# SCH_esp32-custom_2024-02-02.net
KiCad netlist of a schematic drawn in EasyEDA
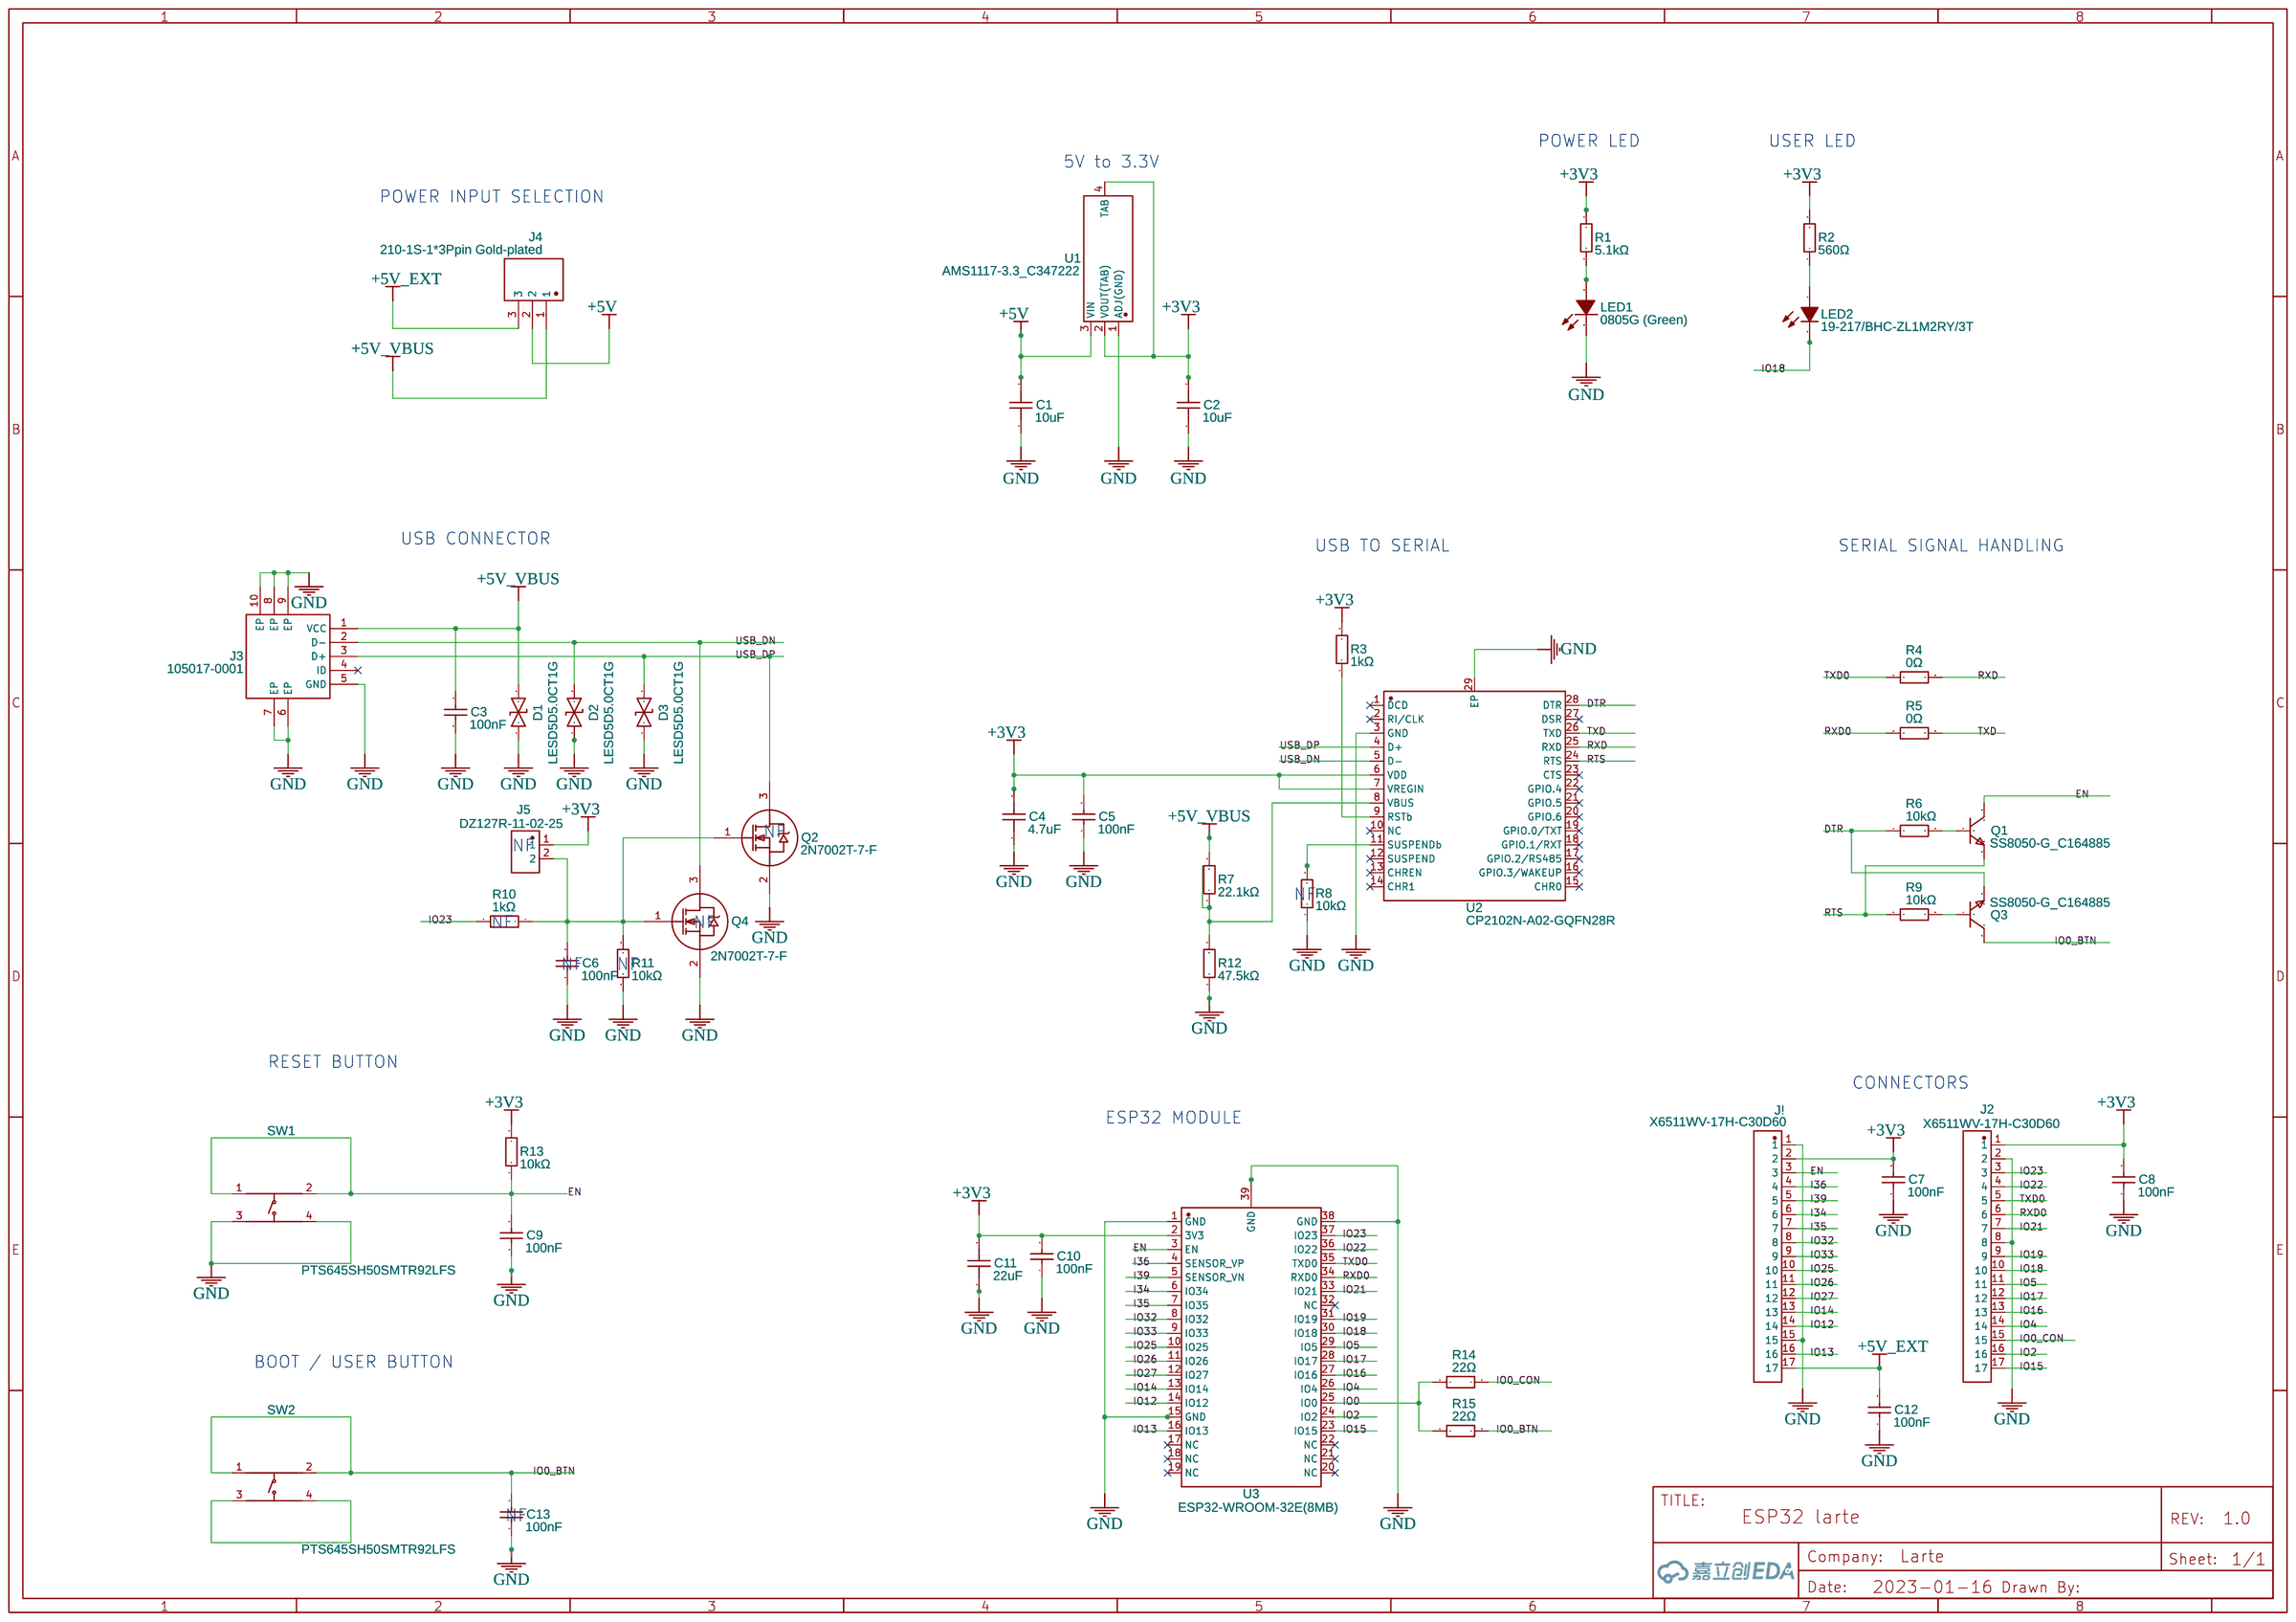
[diagram p0: schematic sheet]

(export (version "E")
  (design (tool "Eeschema 10.0.6"))
  (components
    (comp (ref "C1")
      (value "10uF")
      (fields
        (field (name "Manufacturer Part") "CL05A106MP5NUNC")
        (field (name "Manufacturer") "SAMSUNG(三星)")
      )
      (libsource (lib "") (part "CL05A106MP5NUNC_C315248"))
    )
    (comp (ref "C2")
      (value "10uF")
      (fields
        (field (name "Manufacturer Part") "CL05A106MP5NUNC")
        (field (name "Manufacturer") "SAMSUNG(三星)")
      )
      (libsource (lib "") (part "CL05A106MP5NUNC_C315248"))
    )
    (comp (ref "C3")
      (value "100nF")
      (fields
        (field (name "Manufacturer Part") "CL05B104KO5NNNC")
        (field (name "Manufacturer") "SAMSUNG(三星)")
      )
      (libsource (lib "") (part "CL05B104KO5NNNC"))
    )
    (comp (ref "C4")
      (value "4.7uF")
      (fields
        (field (name "Manufacturer Part") "CL05A475KP5NRNC")
        (field (name "Manufacturer") "SAMSUNG(三星)")
      )
      (libsource (lib "") (part "CL05A475KP5NRNC"))
    )
    (comp (ref "C5")
      (value "100nF")
      (fields
        (field (name "Manufacturer Part") "CL05B104KO5NNNC")
        (field (name "Manufacturer") "SAMSUNG(三星)")
      )
      (libsource (lib "") (part "CL05B104KO5NNNC"))
    )
    (comp (ref "C6")
      (value "100nF")
      (fields
        (field (name "Manufacturer Part") "CL05B104KO5NNNC")
        (field (name "Manufacturer") "SAMSUNG(三星)")
      )
      (libsource (lib "") (part "CL05B104KO5NNNC"))
    )
    (comp (ref "C7")
      (value "100nF")
      (fields
        (field (name "Manufacturer Part") "CL05B104KO5NNNC")
        (field (name "Manufacturer") "SAMSUNG(三星)")
      )
      (libsource (lib "") (part "CL05B104KO5NNNC"))
    )
    (comp (ref "C8")
      (value "100nF")
      (fields
        (field (name "Manufacturer Part") "CL05B104KO5NNNC")
        (field (name "Manufacturer") "SAMSUNG(三星)")
      )
      (libsource (lib "") (part "CL05B104KO5NNNC"))
    )
    (comp (ref "C9")
      (value "100nF")
      (fields
        (field (name "Manufacturer Part") "CL05B104KO5NNNC")
        (field (name "Manufacturer") "SAMSUNG(三星)")
      )
      (libsource (lib "") (part "CL05B104KO5NNNC"))
    )
    (comp (ref "C10")
      (value "100nF")
      (fields
        (field (name "Manufacturer Part") "CL05B104KO5NNNC")
        (field (name "Manufacturer") "SAMSUNG(三星)")
      )
      (libsource (lib "") (part "CL05B104KO5NNNC"))
    )
    (comp (ref "C11")
      (value "22uF")
      (fields
        (field (name "Manufacturer Part") "CL21A226MAYNNNE")
        (field (name "Manufacturer") "SAMSUNG(三星)")
      )
      (libsource (lib "") (part "CL21A226MAYNNNE"))
    )
    (comp (ref "C12")
      (value "100nF")
      (fields
        (field (name "Manufacturer Part") "CL05B104KO5NNNC")
        (field (name "Manufacturer") "SAMSUNG(三星)")
      )
      (libsource (lib "") (part "CL05B104KO5NNNC"))
    )
    (comp (ref "C13")
      (value "100nF")
      (fields
        (field (name "Manufacturer Part") "CL05B104KO5NNNC")
        (field (name "Manufacturer") "SAMSUNG(三星)")
      )
      (libsource (lib "") (part "CL05B104KO5NNNC"))
    )
    (comp (ref "D1")
      (value "LESD5D5.0CT1G")
      (fields (field (name "Manufacturer") "LRC(乐山无线电)"))
      (libsource (lib "") (part "LESD5D5.0CT1G"))
    )
    (comp (ref "D2")
      (value "LESD5D5.0CT1G")
      (fields (field (name "Manufacturer") "LRC(乐山无线电)"))
      (libsource (lib "") (part "LESD5D5.0CT1G"))
    )
    (comp (ref "D3")
      (value "LESD5D5.0CT1G")
      (fields (field (name "Manufacturer") "LRC(乐山无线电)"))
      (libsource (lib "") (part "LESD5D5.0CT1G"))
    )
    (comp (ref "J!")
      (value "X6511WV-17H-C30D60")
      (fields
        (field (name "Manufacturer Part") "X6511WV-17H-C60D30")
        (field (name "Manufacturer") "XKB Connectivity(中国星坤)")
      )
      (libsource (lib "") (part "X6511WV-17H-C30D60_1"))
    )
    (comp (ref "J2")
      (value "X6511WV-17H-C30D60")
      (fields
        (field (name "Manufacturer Part") "X6511WV-17H-C60D30")
        (field (name "Manufacturer") "XKB Connectivity(中国星坤)")
      )
      (libsource (lib "") (part "X6511WV-17H-C30D60"))
    )
    (comp (ref "J3")
      (value "105017-0001")
      (fields (field (name "Manufacturer Part") "1050170001") (field (name "Manufacturer") "MOLEX"))
      (libsource (lib "") (part "105017-0001"))
    )
    (comp (ref "J4")
      (value "210-1S-1*3Ppin Gold-plated")
      (fields (field (name "Manufacturer Part") "B-2101S03P-A110") (field (name "Manufacturer") "Ckmtw(灿科盟)"))
      (libsource (lib "") (part "210-1S-1*3Ppin Gold-plated"))
    )
    (comp (ref "J5")
      (value "DZ127R-11-02-25")
      (fields (field (name "Manufacturer") "DEALON(德艺隆)"))
      (libsource (lib "") (part "DZ127R-11-02-25"))
    )
    (comp (ref "LED1")
      (value "0805G (Green)")
      (fields (field (name "Manufacturer Part") "KT-0805翠绿 (SMT业务专用)"))
      (libsource (lib "") (part "0805G (Green)"))
    )
    (comp (ref "LED2")
      (value "19-217/BHC-ZL1M2RY/3T")
      (fields (field (name "Manufacturer") "EVERLIGHT(亿光)"))
      (libsource (lib "") (part "19-217/BHC-ZL1M2RY/3T"))
    )
    (comp (ref "Q1")
      (value "SS8050-G_C164885")
      (fields (field (name "Manufacturer Part") "SS8050-G") (field (name "Manufacturer") "CJ(江苏长电/长晶)"))
      (libsource (lib "") (part "SS8050-G_C164885"))
    )
    (comp (ref "Q2")
      (value "2N7002T-7-F")
      (fields (field (name "Manufacturer") "DIODES(美台)"))
      (libsource (lib "") (part "2N7002T-7-F"))
    )
    (comp (ref "Q3")
      (value "SS8050-G_C164885")
      (fields (field (name "Manufacturer Part") "SS8050-G") (field (name "Manufacturer") "CJ(江苏长电/长晶)"))
      (libsource (lib "") (part "SS8050-G_C164885_1"))
    )
    (comp (ref "Q4")
      (value "2N7002T-7-F")
      (fields (field (name "Manufacturer") "DIODES(美台)"))
      (libsource (lib "") (part "2N7002T-7-F"))
    )
    (comp (ref "R1")
      (value "5.1kΩ")
      (fields
        (field (name "Manufacturer Part") "0402WGF5101TCE")
        (field (name "Manufacturer") "UNI-ROYAL(厚声)")
      )
      (libsource (lib "") (part "0402WGF5101TCE"))
    )
    (comp (ref "R2")
      (value "560Ω")
      (fields
        (field (name "Manufacturer Part") "0402WGF5600TCE")
        (field (name "Manufacturer") "UNI-ROYAL(厚声)")
      )
      (libsource (lib "") (part "0402WGF5600TCE"))
    )
    (comp (ref "R3")
      (value "1kΩ")
      (fields
        (field (name "Manufacturer Part") "0402WGF1001TCE")
        (field (name "Manufacturer") "UNI-ROYAL(厚声)")
      )
      (libsource (lib "") (part "0402WGF1001TCE_1"))
    )
    (comp (ref "R4")
      (value "0Ω")
      (fields
        (field (name "Manufacturer Part") "0402WGF0000TCE")
        (field (name "Manufacturer") "UNI-ROYAL(厚声)")
      )
      (libsource (lib "") (part "0402WGF0000TCE"))
    )
    (comp (ref "R5")
      (value "0Ω")
      (fields
        (field (name "Manufacturer Part") "0402WGF0000TCE")
        (field (name "Manufacturer") "UNI-ROYAL(厚声)")
      )
      (libsource (lib "") (part "0402WGF0000TCE"))
    )
    (comp (ref "R6")
      (value "10kΩ")
      (fields
        (field (name "Manufacturer Part") "0402WGF1002TCE")
        (field (name "Manufacturer") "UNI-ROYAL(厚声)")
      )
      (libsource (lib "") (part "0402WGF1002TCE_1"))
    )
    (comp (ref "R7")
      (value "22.1kΩ")
      (fields
        (field (name "Manufacturer Part") "0402WGF2212TCE")
        (field (name "Manufacturer") "UNI-ROYAL(厚声)")
      )
      (libsource (lib "") (part "0402WGF2212TCE"))
    )
    (comp (ref "R8")
      (value "10kΩ")
      (fields
        (field (name "Manufacturer Part") "0402WGF1002TCE")
        (field (name "Manufacturer") "UNI-ROYAL(厚声)")
      )
      (libsource (lib "") (part "0402WGF1002TCE"))
    )
    (comp (ref "R9")
      (value "10kΩ")
      (fields
        (field (name "Manufacturer Part") "0402WGF1002TCE")
        (field (name "Manufacturer") "UNI-ROYAL(厚声)")
      )
      (libsource (lib "") (part "0402WGF1002TCE_1"))
    )
    (comp (ref "R10")
      (value "1kΩ")
      (fields
        (field (name "Manufacturer Part") "0402WGF1001TCE")
        (field (name "Manufacturer") "UNI-ROYAL(厚声)")
      )
      (libsource (lib "") (part "0402WGF1001TCE"))
    )
    (comp (ref "R11")
      (value "10kΩ")
      (fields
        (field (name "Manufacturer Part") "0402WGF1002TCE")
        (field (name "Manufacturer") "UNI-ROYAL(厚声)")
      )
      (libsource (lib "") (part "0402WGF1002TCE"))
    )
    (comp (ref "R12")
      (value "47.5kΩ")
      (fields
        (field (name "Manufacturer Part") "0402WGF4752TCE")
        (field (name "Manufacturer") "UNI-ROYAL(厚声)")
      )
      (libsource (lib "") (part "0402WGF4752TCE"))
    )
    (comp (ref "R13")
      (value "10kΩ")
      (fields
        (field (name "Manufacturer Part") "0402WGF1002TCE")
        (field (name "Manufacturer") "UNI-ROYAL(厚声)")
      )
      (libsource (lib "") (part "0402WGF1002TCE"))
    )
    (comp (ref "R14")
      (value "22Ω")
      (fields
        (field (name "Manufacturer Part") "0402WGF220JTCE")
        (field (name "Manufacturer") "UNI-ROYAL(厚声)")
      )
      (libsource (lib "") (part "0402WGF220JTCE"))
    )
    (comp (ref "R15")
      (value "22Ω")
      (fields
        (field (name "Manufacturer Part") "0402WGF220JTCE")
        (field (name "Manufacturer") "UNI-ROYAL(厚声)")
      )
      (libsource (lib "") (part "0402WGF220JTCE"))
    )
    (comp (ref "SW1")
      (value "PTS645SH50SMTR92LFS")
      (fields (field (name "Manufacturer") "C&K"))
      (libsource (lib "") (part "PTS645SH50SMTR92LFS"))
    )
    (comp (ref "SW2")
      (value "PTS645SH50SMTR92LFS")
      (fields (field (name "Manufacturer") "C&K"))
      (libsource (lib "") (part "PTS645SH50SMTR92LFS"))
    )
    (comp (ref "U1")
      (value "AMS1117-3.3_C347222")
      (fields (field (name "Manufacturer Part") "AMS1117-3.3") (field (name "Manufacturer") "UMW(广东友台半导体)"))
      (libsource (lib "") (part "AMS1117-3.3_C347222"))
    )
    (comp (ref "U2")
      (value "CP2102N-A02-GQFN28R")
      (fields (field (name "Manufacturer") "SILICON LABS(芯科)"))
      (libsource (lib "") (part "CP2102N-A02-GQFN28R"))
    )
    (comp (ref "U3")
      (value "ESP32-WROOM-32E(8MB)")
      (fields
        (field (name "Manufacturer Part") "ESP32-WROOM-32E-N8")
        (field (name "Manufacturer") "ESPRESSIF(乐鑫)")
      )
      (libsource (lib "") (part "ESP32-WROOM-32E(8MB)"))
    )
  )
  (nets
    (net (code "1") (name "+3V3") (class "Default")
      (node (ref "C10") (pin "2") (pinfunction "2_2") (pintype "input"))
      (node (ref "C11") (pin "2") (pinfunction "2_2") (pintype "unspecified"))
      (node (ref "C2") (pin "2") (pinfunction "2_2") (pintype "unspecified"))
      (node (ref "C4") (pin "2") (pinfunction "2_2") (pintype "unspecified"))
      (node (ref "C5") (pin "2") (pinfunction "2_2") (pintype "input"))
      (node (ref "C7") (pin "2") (pinfunction "2_2") (pintype "input"))
      (node (ref "C8") (pin "2") (pinfunction "2_2") (pintype "input"))
      (node (ref "J!") (pin "2") (pinfunction "2_2") (pintype "unspecified"))
      (node (ref "J2") (pin "1") (pinfunction "1_1") (pintype "unspecified"))
      (node (ref "J5") (pin "1") (pinfunction "1_1") (pintype "unspecified"))
      (node (ref "R1") (pin "1") (pinfunction "1_1") (pintype "input"))
      (node (ref "R13") (pin "2") (pinfunction "2_2") (pintype "input"))
      (node (ref "R2") (pin "2") (pinfunction "2_2") (pintype "input"))
      (node (ref "R3") (pin "2") (pinfunction "2_2") (pintype "input"))
      (node (ref "U1") (pin "2") (pinfunction "VOUT(TAB)_2") (pintype "unspecified"))
      (node (ref "U1") (pin "4") (pinfunction "TAB_4") (pintype "unspecified"))
      (node (ref "U2") (pin "6") (pinfunction "VDD_6") (pintype "unspecified"))
      (node (ref "U2") (pin "7") (pinfunction "VREGIN_7") (pintype "unspecified"))
      (node (ref "U3") (pin "2") (pinfunction "3V3_2") (pintype "unspecified"))
    )
    (net (code "2") (name "+5V") (class "Default")
      (node (ref "C1") (pin "2") (pinfunction "2_2") (pintype "unspecified"))
      (node (ref "J4") (pin "2") (pinfunction "2_2") (pintype "unspecified"))
      (node (ref "U1") (pin "3") (pinfunction "VIN_3") (pintype "unspecified"))
    )
    (net (code "3") (name "+5V_EXT") (class "Default")
      (node (ref "C12") (pin "2") (pinfunction "2_2") (pintype "input"))
      (node (ref "J!") (pin "17") (pinfunction "17_17") (pintype "unspecified"))
      (node (ref "J4") (pin "3") (pinfunction "3_3") (pintype "unspecified"))
    )
    (net (code "4") (name "+5V_VBUS") (class "Default")
      (node (ref "C3") (pin "2") (pinfunction "2_2") (pintype "input"))
      (node (ref "D1") (pin "2") (pinfunction "2_2") (pintype "unspecified"))
      (node (ref "J3") (pin "1") (pinfunction "VCC_1") (pintype "unspecified"))
      (node (ref "J4") (pin "1") (pinfunction "1_1") (pintype "unspecified"))
      (node (ref "R7") (pin "2") (pinfunction "2_2") (pintype "input"))
    )
    (net (code "5") (name "/DTR") (class "Default")
      (node (ref "Q3") (pin "2") (pinfunction "E_2") (pintype "unspecified"))
      (node (ref "R6") (pin "1") (pinfunction "1_1") (pintype "input"))
      (node (ref "U2") (pin "28") (pinfunction "DTR_28") (pintype "unspecified"))
    )
    (net (code "6") (name "/EN") (class "Default")
      (node (ref "C9") (pin "2") (pinfunction "2_2") (pintype "input"))
      (node (ref "J!") (pin "3") (pinfunction "3_3") (pintype "unspecified"))
      (node (ref "Q1") (pin "3") (pinfunction "C_3") (pintype "unspecified"))
      (node (ref "R13") (pin "1") (pinfunction "1_1") (pintype "input"))
      (node (ref "SW1") (pin "1") (pinfunction "1_1") (pintype "unspecified"))
      (node (ref "SW1") (pin "2") (pinfunction "2_2") (pintype "unspecified"))
      (node (ref "U3") (pin "3") (pinfunction "EN_3") (pintype "unspecified"))
    )
    (net (code "7") (name "/I34") (class "Default")
      (node (ref "J!") (pin "6") (pinfunction "6_6") (pintype "unspecified"))
      (node (ref "U3") (pin "6") (pinfunction "IO34_6") (pintype "unspecified"))
    )
    (net (code "8") (name "/I35") (class "Default")
      (node (ref "J!") (pin "7") (pinfunction "7_7") (pintype "unspecified"))
      (node (ref "U3") (pin "7") (pinfunction "IO35_7") (pintype "unspecified"))
    )
    (net (code "9") (name "/I36") (class "Default")
      (node (ref "J!") (pin "4") (pinfunction "4_4") (pintype "unspecified"))
      (node (ref "U3") (pin "4") (pinfunction "SENSOR_VP_4") (pintype "unspecified"))
    )
    (net (code "10") (name "/I39") (class "Default")
      (node (ref "J!") (pin "5") (pinfunction "5_5") (pintype "unspecified"))
      (node (ref "U3") (pin "5") (pinfunction "SENSOR_VN_5") (pintype "unspecified"))
    )
    (net (code "11") (name "/IO0") (class "Default")
      (node (ref "R14") (pin "1") (pinfunction "1_1") (pintype "input"))
      (node (ref "R15") (pin "1") (pinfunction "1_1") (pintype "input"))
      (node (ref "U3") (pin "25") (pinfunction "IO0_25") (pintype "unspecified"))
    )
    (net (code "12") (name "/IO0_BTN") (class "Default")
      (node (ref "C13") (pin "2") (pinfunction "2_2") (pintype "input"))
      (node (ref "Q3") (pin "3") (pinfunction "C_3") (pintype "unspecified"))
      (node (ref "R15") (pin "2") (pinfunction "2_2") (pintype "input"))
      (node (ref "SW2") (pin "1") (pinfunction "1_1") (pintype "unspecified"))
      (node (ref "SW2") (pin "2") (pinfunction "2_2") (pintype "unspecified"))
    )
    (net (code "13") (name "/IO0_CON") (class "Default")
      (node (ref "J2") (pin "15") (pinfunction "15_15") (pintype "unspecified"))
      (node (ref "R14") (pin "2") (pinfunction "2_2") (pintype "input"))
    )
    (net (code "14") (name "/IO2") (class "Default")
      (node (ref "J2") (pin "16") (pinfunction "16_16") (pintype "unspecified"))
      (node (ref "U3") (pin "24") (pinfunction "IO2_24") (pintype "unspecified"))
    )
    (net (code "15") (name "/IO4") (class "Default")
      (node (ref "J2") (pin "14") (pinfunction "14_14") (pintype "unspecified"))
      (node (ref "U3") (pin "26") (pinfunction "IO4_26") (pintype "unspecified"))
    )
    (net (code "16") (name "/IO5") (class "Default")
      (node (ref "J2") (pin "11") (pinfunction "11_11") (pintype "unspecified"))
      (node (ref "U3") (pin "29") (pinfunction "IO5_29") (pintype "unspecified"))
    )
    (net (code "17") (name "/IO12") (class "Default")
      (node (ref "J!") (pin "14") (pinfunction "14_14") (pintype "unspecified"))
      (node (ref "U3") (pin "14") (pinfunction "IO12_14") (pintype "unspecified"))
    )
    (net (code "18") (name "/IO13") (class "Default")
      (node (ref "J!") (pin "16") (pinfunction "16_16") (pintype "unspecified"))
      (node (ref "U3") (pin "16") (pinfunction "IO13_16") (pintype "unspecified"))
    )
    (net (code "19") (name "/IO14") (class "Default")
      (node (ref "J!") (pin "13") (pinfunction "13_13") (pintype "unspecified"))
      (node (ref "U3") (pin "13") (pinfunction "IO14_13") (pintype "unspecified"))
    )
    (net (code "20") (name "/IO15") (class "Default")
      (node (ref "J2") (pin "17") (pinfunction "17_17") (pintype "unspecified"))
      (node (ref "U3") (pin "23") (pinfunction "IO15_23") (pintype "unspecified"))
    )
    (net (code "21") (name "/IO16") (class "Default")
      (node (ref "J2") (pin "13") (pinfunction "13_13") (pintype "unspecified"))
      (node (ref "U3") (pin "27") (pinfunction "IO16_27") (pintype "unspecified"))
    )
    (net (code "22") (name "/IO17") (class "Default")
      (node (ref "J2") (pin "12") (pinfunction "12_12") (pintype "unspecified"))
      (node (ref "U3") (pin "28") (pinfunction "IO17_28") (pintype "unspecified"))
    )
    (net (code "23") (name "/IO18") (class "Default")
      (node (ref "J2") (pin "10") (pinfunction "10_10") (pintype "unspecified"))
      (node (ref "LED2") (pin "2") (pinfunction "C_2") (pintype "input"))
      (node (ref "U3") (pin "30") (pinfunction "IO18_30") (pintype "unspecified"))
    )
    (net (code "24") (name "/IO19") (class "Default")
      (node (ref "J2") (pin "9") (pinfunction "9_9") (pintype "unspecified"))
      (node (ref "U3") (pin "31") (pinfunction "IO19_31") (pintype "unspecified"))
    )
    (net (code "25") (name "/IO21") (class "Default")
      (node (ref "J2") (pin "7") (pinfunction "7_7") (pintype "unspecified"))
      (node (ref "U3") (pin "33") (pinfunction "IO21_33") (pintype "unspecified"))
    )
    (net (code "26") (name "/IO22") (class "Default")
      (node (ref "J2") (pin "4") (pinfunction "4_4") (pintype "unspecified"))
      (node (ref "U3") (pin "36") (pinfunction "IO22_36") (pintype "unspecified"))
    )
    (net (code "27") (name "/IO23") (class "Default")
      (node (ref "J2") (pin "3") (pinfunction "3_3") (pintype "unspecified"))
      (node (ref "R10") (pin "2") (pinfunction "2_2") (pintype "input"))
      (node (ref "U3") (pin "37") (pinfunction "IO23_37") (pintype "unspecified"))
    )
    (net (code "28") (name "/IO25") (class "Default")
      (node (ref "J!") (pin "10") (pinfunction "10_10") (pintype "unspecified"))
      (node (ref "U3") (pin "10") (pinfunction "IO25_10") (pintype "unspecified"))
    )
    (net (code "29") (name "/IO26") (class "Default")
      (node (ref "J!") (pin "11") (pinfunction "11_11") (pintype "unspecified"))
      (node (ref "U3") (pin "11") (pinfunction "IO26_11") (pintype "unspecified"))
    )
    (net (code "30") (name "/IO27") (class "Default")
      (node (ref "J!") (pin "12") (pinfunction "12_12") (pintype "unspecified"))
      (node (ref "U3") (pin "12") (pinfunction "IO27_12") (pintype "unspecified"))
    )
    (net (code "31") (name "/IO32") (class "Default")
      (node (ref "J!") (pin "8") (pinfunction "8_8") (pintype "unspecified"))
      (node (ref "U3") (pin "8") (pinfunction "IO32_8") (pintype "unspecified"))
    )
    (net (code "32") (name "/IO33") (class "Default")
      (node (ref "J!") (pin "9") (pinfunction "9_9") (pintype "unspecified"))
      (node (ref "U3") (pin "9") (pinfunction "IO33_9") (pintype "unspecified"))
    )
    (net (code "33") (name "/RTS") (class "Default")
      (node (ref "Q1") (pin "2") (pinfunction "E_2") (pintype "unspecified"))
      (node (ref "R9") (pin "1") (pinfunction "1_1") (pintype "input"))
      (node (ref "U2") (pin "24") (pinfunction "RTS_24") (pintype "unspecified"))
    )
    (net (code "34") (name "/RXD") (class "Default")
      (node (ref "R4") (pin "2") (pinfunction "2_2") (pintype "input"))
      (node (ref "U2") (pin "25") (pinfunction "RXD_25") (pintype "unspecified"))
    )
    (net (code "35") (name "/RXD0") (class "Default")
      (node (ref "J2") (pin "6") (pinfunction "6_6") (pintype "unspecified"))
      (node (ref "R5") (pin "1") (pinfunction "1_1") (pintype "input"))
      (node (ref "U3") (pin "34") (pinfunction "RXD0_34") (pintype "unspecified"))
    )
    (net (code "36") (name "/TXD") (class "Default")
      (node (ref "R5") (pin "2") (pinfunction "2_2") (pintype "input"))
      (node (ref "U2") (pin "26") (pinfunction "TXD_26") (pintype "unspecified"))
    )
    (net (code "37") (name "/TXD0") (class "Default")
      (node (ref "J2") (pin "5") (pinfunction "5_5") (pintype "unspecified"))
      (node (ref "R4") (pin "1") (pinfunction "1_1") (pintype "input"))
      (node (ref "U3") (pin "35") (pinfunction "TXD0_35") (pintype "unspecified"))
    )
    (net (code "38") (name "/USB_DN") (class "Default")
      (node (ref "D2") (pin "2") (pinfunction "2_2") (pintype "unspecified"))
      (node (ref "J3") (pin "2") (pinfunction "D-_2") (pintype "unspecified"))
      (node (ref "Q4") (pin "3") (pinfunction "D_3") (pintype "unspecified"))
      (node (ref "U2") (pin "5") (pinfunction "D-_5") (pintype "unspecified"))
    )
    (net (code "39") (name "/USB_DP") (class "Default")
      (node (ref "D3") (pin "2") (pinfunction "2_2") (pintype "unspecified"))
      (node (ref "J3") (pin "3") (pinfunction "D+_3") (pintype "unspecified"))
      (node (ref "Q2") (pin "3") (pinfunction "D_3") (pintype "unspecified"))
      (node (ref "U2") (pin "4") (pinfunction "D+_4") (pintype "unspecified"))
    )
    (net (code "40") (name "GND") (class "Default")
      (node (ref "C1") (pin "1") (pinfunction "1_1") (pintype "unspecified"))
      (node (ref "C10") (pin "1") (pinfunction "1_1") (pintype "input"))
      (node (ref "C11") (pin "1") (pinfunction "1_1") (pintype "unspecified"))
      (node (ref "C12") (pin "1") (pinfunction "1_1") (pintype "input"))
      (node (ref "C13") (pin "1") (pinfunction "1_1") (pintype "input"))
      (node (ref "C2") (pin "1") (pinfunction "1_1") (pintype "unspecified"))
      (node (ref "C3") (pin "1") (pinfunction "1_1") (pintype "input"))
      (node (ref "C4") (pin "1") (pinfunction "1_1") (pintype "unspecified"))
      (node (ref "C5") (pin "1") (pinfunction "1_1") (pintype "input"))
      (node (ref "C6") (pin "1") (pinfunction "1_1") (pintype "input"))
      (node (ref "C7") (pin "1") (pinfunction "1_1") (pintype "input"))
      (node (ref "C8") (pin "1") (pinfunction "1_1") (pintype "input"))
      (node (ref "C9") (pin "1") (pinfunction "1_1") (pintype "input"))
      (node (ref "D1") (pin "1") (pinfunction "1_1") (pintype "unspecified"))
      (node (ref "D2") (pin "1") (pinfunction "1_1") (pintype "unspecified"))
      (node (ref "D3") (pin "1") (pinfunction "1_1") (pintype "unspecified"))
      (node (ref "J!") (pin "1") (pinfunction "1_1") (pintype "unspecified"))
      (node (ref "J!") (pin "15") (pinfunction "15_15") (pintype "unspecified"))
      (node (ref "J2") (pin "2") (pinfunction "2_2") (pintype "unspecified"))
      (node (ref "J2") (pin "8") (pinfunction "8_8") (pintype "unspecified"))
      (node (ref "J3") (pin "10") (pinfunction "EP_10") (pintype "unspecified"))
      (node (ref "J3") (pin "5") (pinfunction "GND_5") (pintype "unspecified"))
      (node (ref "J3") (pin "6") (pinfunction "EP_6") (pintype "unspecified"))
      (node (ref "J3") (pin "7") (pinfunction "EP_7") (pintype "unspecified"))
      (node (ref "J3") (pin "8") (pinfunction "EP_8") (pintype "unspecified"))
      (node (ref "J3") (pin "9") (pinfunction "EP_9") (pintype "unspecified"))
      (node (ref "LED1") (pin "1") (pinfunction "K_1") (pintype "unspecified"))
      (node (ref "Q2") (pin "2") (pinfunction "S_2") (pintype "unspecified"))
      (node (ref "Q4") (pin "2") (pinfunction "S_2") (pintype "unspecified"))
      (node (ref "R11") (pin "1") (pinfunction "1_1") (pintype "input"))
      (node (ref "R12") (pin "1") (pinfunction "1_1") (pintype "input"))
      (node (ref "R8") (pin "1") (pinfunction "1_1") (pintype "input"))
      (node (ref "SW1") (pin "3") (pinfunction "3_3") (pintype "unspecified"))
      (node (ref "SW1") (pin "4") (pinfunction "4_4") (pintype "unspecified"))
      (node (ref "U1") (pin "1") (pinfunction "ADJ(GND)_1") (pintype "unspecified"))
      (node (ref "U2") (pin "29") (pinfunction "EP_29") (pintype "unspecified"))
      (node (ref "U2") (pin "3") (pinfunction "GND_3") (pintype "unspecified"))
      (node (ref "U3") (pin "1") (pinfunction "GND_1") (pintype "unspecified"))
      (node (ref "U3") (pin "15") (pinfunction "GND_15") (pintype "unspecified"))
      (node (ref "U3") (pin "38") (pinfunction "GND_38") (pintype "unspecified"))
      (node (ref "U3") (pin "39") (pinfunction "GND_39") (pintype "unspecified"))
    )
    (net (code "41") (name "Net-(LED1-A)") (class "Default")
      (node (ref "LED1") (pin "2") (pinfunction "A_2") (pintype "unspecified"))
      (node (ref "R1") (pin "2") (pinfunction "2_2") (pintype "input"))
    )
    (net (code "42") (name "Net-(LED2-A)") (class "Default")
      (node (ref "LED2") (pin "1") (pinfunction "A_1") (pintype "input"))
      (node (ref "R2") (pin "1") (pinfunction "1_1") (pintype "input"))
    )
    (net (code "43") (name "Net-(Q1-B)") (class "Default")
      (node (ref "Q1") (pin "1") (pinfunction "B_1") (pintype "unspecified"))
      (node (ref "R6") (pin "2") (pinfunction "2_2") (pintype "input"))
    )
    (net (code "44") (name "Net-(Q2-G)") (class "Default")
      (node (ref "C6") (pin "2") (pinfunction "2_2") (pintype "input"))
      (node (ref "J5") (pin "2") (pinfunction "2_2") (pintype "unspecified"))
      (node (ref "Q2") (pin "1") (pinfunction "G_1") (pintype "unspecified"))
      (node (ref "Q4") (pin "1") (pinfunction "G_1") (pintype "unspecified"))
      (node (ref "R10") (pin "1") (pinfunction "1_1") (pintype "input"))
      (node (ref "R11") (pin "2") (pinfunction "2_2") (pintype "input"))
    )
    (net (code "45") (name "Net-(Q3-B)") (class "Default")
      (node (ref "Q3") (pin "1") (pinfunction "B_1") (pintype "unspecified"))
      (node (ref "R9") (pin "2") (pinfunction "2_2") (pintype "input"))
    )
    (net (code "46") (name "Net-(SW2-Pad3)") (class "Default")
      (node (ref "SW2") (pin "3") (pinfunction "3_3") (pintype "unspecified"))
      (node (ref "SW2") (pin "4") (pinfunction "4_4") (pintype "unspecified"))
    )
    (net (code "47") (name "Net-(U2-RSTb)") (class "Default")
      (node (ref "R3") (pin "1") (pinfunction "1_1") (pintype "input"))
      (node (ref "U2") (pin "9") (pinfunction "RSTb_9") (pintype "unspecified"))
    )
    (net (code "48") (name "Net-(U2-SUSPENDb)") (class "Default")
      (node (ref "R8") (pin "2") (pinfunction "2_2") (pintype "input"))
      (node (ref "U2") (pin "11") (pinfunction "SUSPENDb_11") (pintype "unspecified"))
    )
    (net (code "49") (name "Net-(U2-VBUS)") (class "Default")
      (node (ref "R12") (pin "2") (pinfunction "2_2") (pintype "input"))
      (node (ref "R7") (pin "1") (pinfunction "1_1") (pintype "input"))
      (node (ref "U2") (pin "8") (pinfunction "VBUS_8") (pintype "unspecified"))
    )
    (net (code "50") (name "unconnected-(J3-ID-Pad4)") (class "Default")
      (node (ref "J3") (pin "4") (pinfunction "ID_4") (pintype "unspecified+no_connect"))
    )
    (net (code "51") (name "unconnected-(U2-CHR0-Pad15)") (class "Default")
      (node (ref "U2") (pin "15") (pinfunction "CHR0_15") (pintype "unspecified+no_connect"))
    )
    (net (code "52") (name "unconnected-(U2-CHR1-Pad14)") (class "Default")
      (node (ref "U2") (pin "14") (pinfunction "CHR1_14") (pintype "unspecified+no_connect"))
    )
    (net (code "53") (name "unconnected-(U2-CHREN-Pad13)") (class "Default")
      (node (ref "U2") (pin "13") (pinfunction "CHREN_13") (pintype "unspecified+no_connect"))
    )
    (net (code "54") (name "unconnected-(U2-CTS-Pad23)") (class "Default")
      (node (ref "U2") (pin "23") (pinfunction "CTS_23") (pintype "unspecified+no_connect"))
    )
    (net (code "55") (name "unconnected-(U2-DCD-Pad1)") (class "Default")
      (node (ref "U2") (pin "1") (pinfunction "DCD_1") (pintype "unspecified+no_connect"))
    )
    (net (code "56") (name "unconnected-(U2-DSR-Pad27)") (class "Default")
      (node (ref "U2") (pin "27") (pinfunction "DSR_27") (pintype "unspecified+no_connect"))
    )
    (net (code "57") (name "unconnected-(U2-GPIO.0{slash}TXT-Pad19)") (class "Default")
      (node (ref "U2") (pin "19") (pinfunction "GPIO.0/TXT_19") (pintype "unspecified+no_connect"))
    )
    (net (code "58") (name "unconnected-(U2-GPIO.1{slash}RXT-Pad18)") (class "Default")
      (node (ref "U2") (pin "18") (pinfunction "GPIO.1/RXT_18") (pintype "unspecified+no_connect"))
    )
    (net (code "59") (name "unconnected-(U2-GPIO.2{slash}RS485-Pad17)") (class "Default")
      (node (ref "U2") (pin "17") (pinfunction "GPIO.2/RS485_17") (pintype "unspecified+no_connect"))
    )
    (net (code "60") (name "unconnected-(U2-GPIO.3{slash}WAKEUP-Pad16)") (class "Default")
      (node (ref "U2") (pin "16") (pinfunction "GPIO.3/WAKEUP_16") (pintype "unspecified+no_connect"))
    )
    (net (code "61") (name "unconnected-(U2-GPIO.4-Pad22)") (class "Default")
      (node (ref "U2") (pin "22") (pinfunction "GPIO.4_22") (pintype "unspecified+no_connect"))
    )
    (net (code "62") (name "unconnected-(U2-GPIO.5-Pad21)") (class "Default")
      (node (ref "U2") (pin "21") (pinfunction "GPIO.5_21") (pintype "unspecified+no_connect"))
    )
    (net (code "63") (name "unconnected-(U2-GPIO.6-Pad20)") (class "Default")
      (node (ref "U2") (pin "20") (pinfunction "GPIO.6_20") (pintype "unspecified+no_connect"))
    )
    (net (code "64") (name "unconnected-(U2-NC-Pad10)") (class "Default")
      (node (ref "U2") (pin "10") (pinfunction "NC_10") (pintype "unspecified+no_connect"))
    )
    (net (code "65") (name "unconnected-(U2-RI{slash}CLK-Pad2)") (class "Default")
      (node (ref "U2") (pin "2") (pinfunction "RI/CLK_2") (pintype "unspecified+no_connect"))
    )
    (net (code "66") (name "unconnected-(U2-SUSPEND-Pad12)") (class "Default")
      (node (ref "U2") (pin "12") (pinfunction "SUSPEND_12") (pintype "unspecified+no_connect"))
    )
    (net (code "67") (name "unconnected-(U3-NC-Pad17)") (class "Default")
      (node (ref "U3") (pin "17") (pinfunction "NC_17") (pintype "unspecified+no_connect"))
    )
    (net (code "68") (name "unconnected-(U3-NC-Pad18)") (class "Default")
      (node (ref "U3") (pin "18") (pinfunction "NC_18") (pintype "unspecified+no_connect"))
    )
    (net (code "69") (name "unconnected-(U3-NC-Pad19)") (class "Default")
      (node (ref "U3") (pin "19") (pinfunction "NC_19") (pintype "unspecified+no_connect"))
    )
    (net (code "70") (name "unconnected-(U3-NC-Pad20)") (class "Default")
      (node (ref "U3") (pin "20") (pinfunction "NC_20") (pintype "unspecified+no_connect"))
    )
    (net (code "71") (name "unconnected-(U3-NC-Pad21)") (class "Default")
      (node (ref "U3") (pin "21") (pinfunction "NC_21") (pintype "unspecified+no_connect"))
    )
    (net (code "72") (name "unconnected-(U3-NC-Pad22)") (class "Default")
      (node (ref "U3") (pin "22") (pinfunction "NC_22") (pintype "unspecified+no_connect"))
    )
    (net (code "73") (name "unconnected-(U3-NC-Pad32)") (class "Default")
      (node (ref "U3") (pin "32") (pinfunction "NC_32") (pintype "unspecified+no_connect"))
    )
  )
)
